# 05_CAMERA_HDMI.net
KiCad netlist of a schematic drawn in Altium Designer
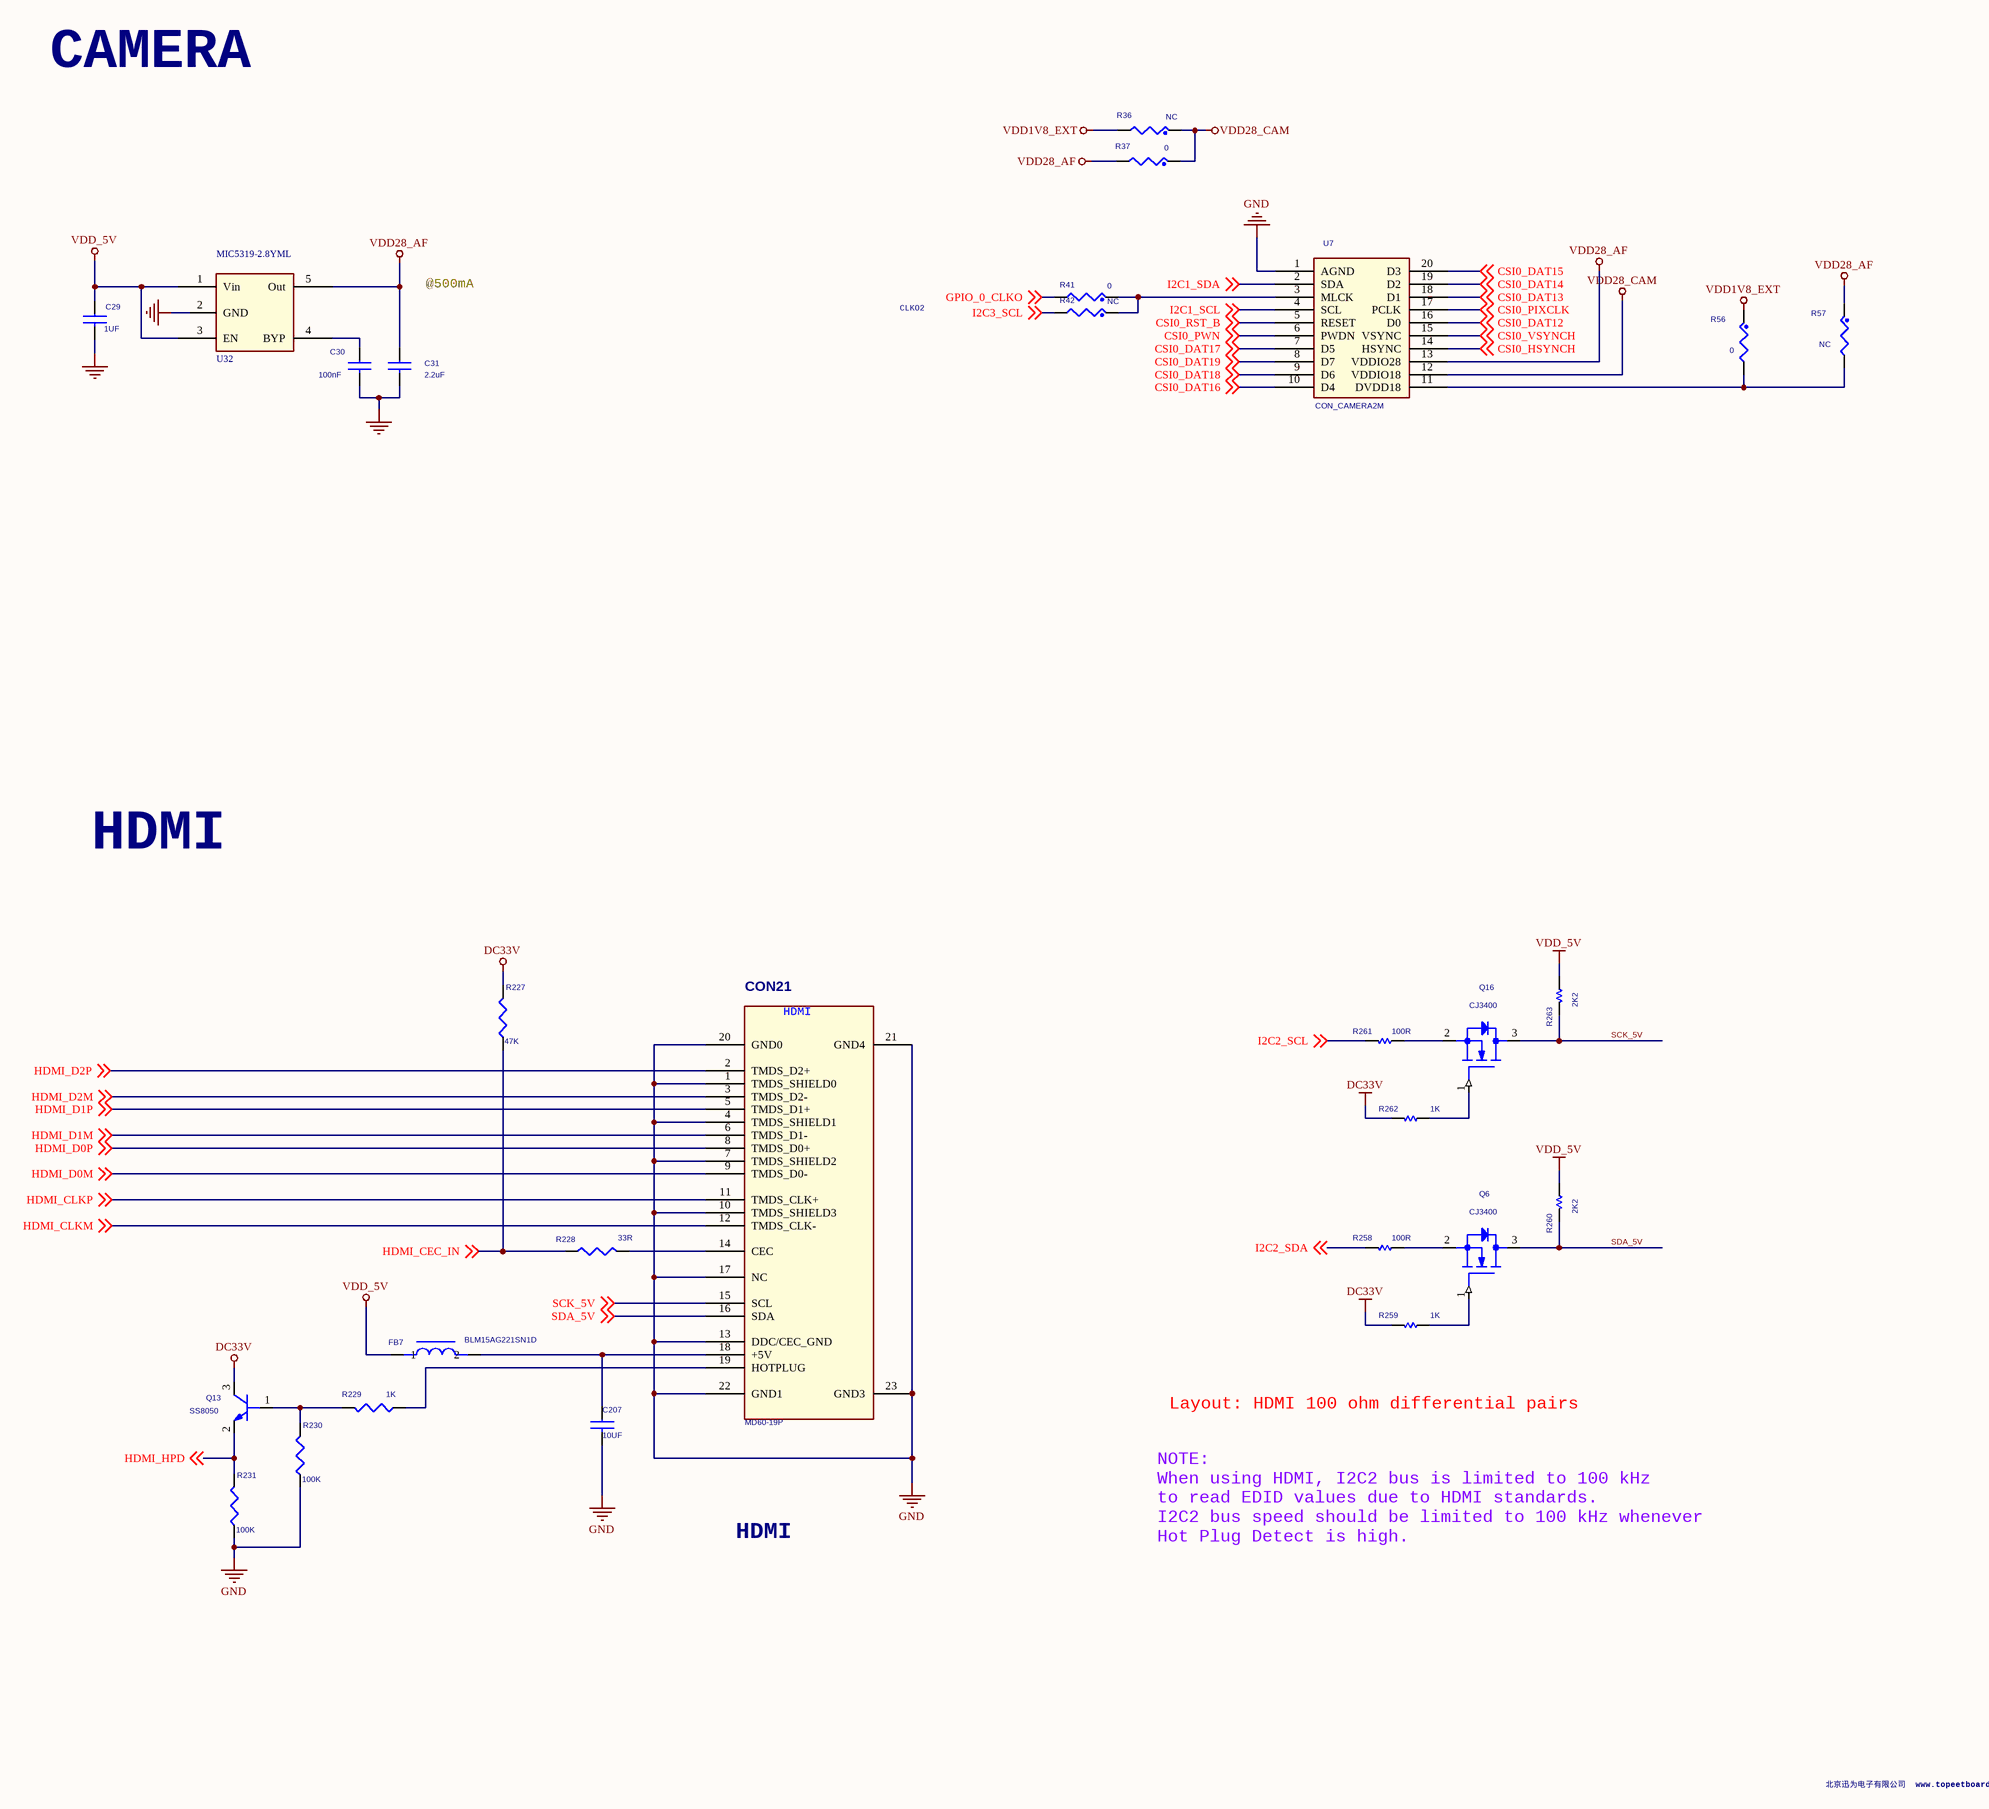
[diagram p0: 05 CAMERA, HDMI.SchDoc]

(export (version "E")
  (design (tool "Eeschema 10.0.6"))
  (components
    (comp (ref "C29") (value "1UF") (footprint "C0603") (libsource (lib "*") (part "C0603_0")))
    (comp (ref "C30") (value "100nF") (footprint "C0603") (libsource (lib "*") (part "C0603_0")))
    (comp (ref "C31") (value "2.2uF") (footprint "C0603") (libsource (lib "*") (part "C0603_0")))
    (comp (ref "C207") (value "10UF") (footprint "C1608") (libsource (lib "*") (part "C1608_Dup1")))
    (comp (ref "CON21") (value "MD60-19P") (footprint "MD60-19P") (libsource (lib "*") (part "MD60-19P_4")))
    (comp (ref "FB7")
      (value "BLM15AG221SN1D")
      (footprint "FB2012")
      (libsource (lib "*") (part "HCB2012KF-300T50_1"))
    )
    (comp (ref "Q6") (value "CJ3400") (libsource (lib "*") (part "NDS351N/SOT_0")))
    (comp (ref "Q13") (value "SS8050") (libsource (lib "*") (part "L14P2/TO_1")))
    (comp (ref "Q16") (value "CJ3400") (libsource (lib "*") (part "NDS351N/SOT_0")))
    (comp (ref "R36")
      (value "NC")
      (description "RES MF 33 OHM 1/16W 5% 0402")
      (fields (field (name "TOLERANCE") "5%"))
      (libsource (lib "*") (part "RES_Dup1"))
    )
    (comp (ref "R37")
      (value "0")
      (description "RES MF 33 OHM 1/16W 5% 0402")
      (fields (field (name "TOLERANCE") "5%"))
      (libsource (lib "*") (part "RES_Dup1"))
    )
    (comp (ref "R41")
      (value "0")
      (description "RES MF 33 OHM 1/16W 5% 0402")
      (fields (field (name "TOLERANCE") "5%"))
      (libsource (lib "*") (part "RES_Dup1"))
    )
    (comp (ref "R42")
      (value "NC")
      (description "RES MF 33 OHM 1/16W 5% 0402")
      (fields (field (name "TOLERANCE") "5%"))
      (libsource (lib "*") (part "RES_Dup1"))
    )
    (comp (ref "R56")
      (value "0")
      (description "RES MF 33 OHM 1/16W 5% 0402")
      (fields (field (name "TOLERANCE") "5%"))
      (libsource (lib "*") (part "RES_Dup1"))
    )
    (comp (ref "R57")
      (value "NC")
      (description "RES MF 33 OHM 1/16W 5% 0402")
      (fields (field (name "TOLERANCE") "5%"))
      (libsource (lib "*") (part "RES_Dup1"))
    )
    (comp (ref "R227") (value "47K") (footprint "R1005") (libsource (lib "*") (part "R1005_0_Dup2")))
    (comp (ref "R228") (value "33R") (footprint "R1005") (libsource (lib "*") (part "R1005_0_Dup2")))
    (comp (ref "R229") (value "1K") (footprint "R1005") (libsource (lib "*") (part "R1005_0_Dup2")))
    (comp (ref "R230") (value "100K") (footprint "R1005") (libsource (lib "*") (part "R1005_0_Dup2")))
    (comp (ref "R231") (value "100K") (footprint "R1005") (libsource (lib "*") (part "R1005_0_Dup2")))
    (comp (ref "R258") (value "100R") (libsource (lib "*") (part "SMALL R1")))
    (comp (ref "R259") (value "1K") (libsource (lib "*") (part "SMALL R1")))
    (comp (ref "R260") (value "2K2") (libsource (lib "*") (part "SMALL R1")))
    (comp (ref "R261") (value "100R") (libsource (lib "*") (part "SMALL R1")))
    (comp (ref "R262") (value "1K") (libsource (lib "*") (part "SMALL R1")))
    (comp (ref "R263") (value "2K2") (libsource (lib "*") (part "SMALL R1")))
    (comp (ref "U7") (value "CON_CAMERA2M") (libsource (lib "*") (part "CON20_0")))
    (comp (ref "U32") (value "MIC5319-2.8YML") (libsource (lib "*") (part "MP1541_0")))
  )
  (nets
    (net (code "1") (name "CSI0_DAT12") (class "Default")
      (node (ref "U7") (pin "16") (pinfunction "D0_16") (pintype "passive"))
    )
    (net (code "2") (name "CSI0_DAT13") (class "Default")
      (node (ref "U7") (pin "18") (pinfunction "D1_18") (pintype "passive"))
    )
    (net (code "3") (name "CSI0_DAT14") (class "Default")
      (node (ref "U7") (pin "19") (pinfunction "D2_19") (pintype "passive"))
    )
    (net (code "4") (name "CSI0_DAT15") (class "Default")
      (node (ref "U7") (pin "20") (pinfunction "D3_20") (pintype "passive"))
    )
    (net (code "5") (name "CSI0_DAT16") (class "Default")
      (node (ref "U7") (pin "10") (pinfunction "D4_10") (pintype "passive"))
    )
    (net (code "6") (name "CSI0_DAT17") (class "Default")
      (node (ref "U7") (pin "7") (pinfunction "D5_7") (pintype "passive"))
    )
    (net (code "7") (name "CSI0_DAT18") (class "Default")
      (node (ref "U7") (pin "9") (pinfunction "D6_9") (pintype "passive"))
    )
    (net (code "8") (name "CSI0_DAT19") (class "Default")
      (node (ref "U7") (pin "8") (pinfunction "D7_8") (pintype "passive"))
    )
    (net (code "9") (name "CSI0_HSYNCH") (class "Default")
      (node (ref "U7") (pin "14") (pinfunction "HSYNC_14") (pintype "passive"))
    )
    (net (code "10") (name "CSI0_PIXCLK") (class "Default")
      (node (ref "U7") (pin "17") (pinfunction "PCLK_17") (pintype "passive"))
    )
    (net (code "11") (name "CSI0_PWN") (class "Default")
      (node (ref "U7") (pin "6") (pinfunction "PWDN_6") (pintype "passive"))
    )
    (net (code "12") (name "CSI0_RST_B") (class "Default")
      (node (ref "U7") (pin "5") (pinfunction "RESET_5") (pintype "passive"))
    )
    (net (code "13") (name "CSI0_VSYNCH") (class "Default")
      (node (ref "U7") (pin "15") (pinfunction "VSYNC_15") (pintype "passive"))
    )
    (net (code "14") (name "DC33V") (class "Default")
      (node (ref "Q13") (pin "3") (pinfunction "COLLECTOR_3") (pintype "passive"))
      (node (ref "R227") (pin "2") (pinfunction "2_2") (pintype "passive"))
      (node (ref "R259") (pin "2") (pinfunction "2_2") (pintype "passive"))
      (node (ref "R262") (pin "2") (pinfunction "2_2") (pintype "passive"))
    )
    (net (code "15") (name "GND") (class "Default")
      (node (ref "C207") (pin "2") (pinfunction "2_2") (pintype "passive"))
      (node (ref "C29") (pin "2") (pinfunction "2_2") (pintype "passive"))
      (node (ref "C30") (pin "2") (pinfunction "2_2") (pintype "passive"))
      (node (ref "C31") (pin "2") (pinfunction "2_2") (pintype "passive"))
      (node (ref "CON21") (pin "1") (pinfunction "TMDS_SHIELD0_1") (pintype "passive"))
      (node (ref "CON21") (pin "10") (pinfunction "TMDS_SHIELD3_10") (pintype "passive"))
      (node (ref "CON21") (pin "13") (pinfunction "DDC/CEC_GND_13") (pintype "passive"))
      (node (ref "CON21") (pin "17") (pinfunction "NC_17") (pintype "passive"))
      (node (ref "CON21") (pin "20") (pinfunction "GND0_20") (pintype "power_in"))
      (node (ref "CON21") (pin "21") (pinfunction "GND4_21") (pintype "power_in"))
      (node (ref "CON21") (pin "22") (pinfunction "GND1_22") (pintype "power_in"))
      (node (ref "CON21") (pin "23") (pinfunction "GND3_23") (pintype "power_in"))
      (node (ref "CON21") (pin "4") (pinfunction "TMDS_SHIELD1_4") (pintype "passive"))
      (node (ref "CON21") (pin "7") (pinfunction "TMDS_SHIELD2_7") (pintype "passive"))
      (node (ref "R230") (pin "1") (pinfunction "1_1") (pintype "passive"))
      (node (ref "R231") (pin "1") (pinfunction "1_1") (pintype "passive"))
      (node (ref "U32") (pin "2") (pinfunction "GND_2") (pintype "passive"))
      (node (ref "U7") (pin "1") (pinfunction "AGND_1") (pintype "power_in"))
    )
    (net (code "16") (name "GPIO_0_CLKO") (class "Default")
      (node (ref "R41") (pin "2") (pinfunction "2_2") (pintype "passive"))
    )
    (net (code "17") (name "HDMI_CEC_IN") (class "Default")
      (node (ref "R227") (pin "1") (pinfunction "1_1") (pintype "passive"))
      (node (ref "R228") (pin "1") (pinfunction "1_1") (pintype "passive"))
    )
    (net (code "18") (name "HDMI_CLKM") (class "Default")
      (node (ref "CON21") (pin "12") (pinfunction "TMDS_CLK-_12") (pintype "passive"))
    )
    (net (code "19") (name "HDMI_CLKP") (class "Default")
      (node (ref "CON21") (pin "11") (pinfunction "TMDS_CLK+_11") (pintype "passive"))
    )
    (net (code "20") (name "HDMI_D0M") (class "Default")
      (node (ref "CON21") (pin "9") (pinfunction "TMDS_D0-_9") (pintype "power_in"))
    )
    (net (code "21") (name "HDMI_D0P") (class "Default")
      (node (ref "CON21") (pin "8") (pinfunction "TMDS_D0+_8") (pintype "passive"))
    )
    (net (code "22") (name "HDMI_D1M") (class "Default")
      (node (ref "CON21") (pin "6") (pinfunction "TMDS_D1-_6") (pintype "passive"))
    )
    (net (code "23") (name "HDMI_D1P") (class "Default")
      (node (ref "CON21") (pin "5") (pinfunction "TMDS_D1+_5") (pintype "passive"))
    )
    (net (code "24") (name "HDMI_D2M") (class "Default")
      (node (ref "CON21") (pin "3") (pinfunction "TMDS_D2-_3") (pintype "passive"))
    )
    (net (code "25") (name "HDMI_D2P") (class "Default")
      (node (ref "CON21") (pin "2") (pinfunction "TMDS_D2+_2") (pintype "passive"))
    )
    (net (code "26") (name "HDMI_HPD") (class "Default")
      (node (ref "Q13") (pin "2") (pinfunction "EMITTER_2") (pintype "passive"))
      (node (ref "R231") (pin "2") (pinfunction "2_2") (pintype "passive"))
    )
    (net (code "27") (name "I2C1_SCL") (class "Default")
      (node (ref "U7") (pin "4") (pinfunction "SCL_4") (pintype "passive"))
    )
    (net (code "28") (name "I2C1_SDA") (class "Default")
      (node (ref "U7") (pin "2") (pinfunction "SDA_2") (pintype "passive"))
    )
    (net (code "29") (name "I2C2_SCL") (class "Default")
      (node (ref "R261") (pin "2") (pinfunction "2_2") (pintype "passive"))
    )
    (net (code "30") (name "I2C2_SDA") (class "Default")
      (node (ref "R258") (pin "2") (pinfunction "2_2") (pintype "passive"))
    )
    (net (code "31") (name "I2C3_SCL") (class "Default")
      (node (ref "R42") (pin "2") (pinfunction "2_2") (pintype "passive"))
    )
    (net (code "32") (name "Net-(CON21-+5V)") (class "Default")
      (node (ref "C207") (pin "1") (pinfunction "1_1") (pintype "passive"))
      (node (ref "CON21") (pin "18") (pinfunction "+5V_18") (pintype "passive"))
      (node (ref "FB7") (pin "2") (pinfunction "2_2") (pintype "passive"))
    )
    (net (code "33") (name "Net-(CON21-CEC)") (class "Default")
      (node (ref "CON21") (pin "14") (pinfunction "CEC_14") (pintype "passive"))
      (node (ref "R228") (pin "2") (pinfunction "2_2") (pintype "passive"))
    )
    (net (code "34") (name "Net-(CON21-HOTPLUG)") (class "Default")
      (node (ref "CON21") (pin "19") (pinfunction "HOTPLUG_19") (pintype "passive"))
      (node (ref "R229") (pin "1") (pinfunction "1_1") (pintype "passive"))
    )
    (net (code "35") (name "Net-(Q6-GATE)") (class "Default")
      (node (ref "Q6") (pin "1") (pinfunction "GATE_1") (pintype "input"))
      (node (ref "R259") (pin "1") (pinfunction "1_1") (pintype "passive"))
    )
    (net (code "36") (name "Net-(Q6-SOURCE)") (class "Default")
      (node (ref "Q6") (pin "2") (pinfunction "SOURCE_2") (pintype "passive"))
      (node (ref "R258") (pin "1") (pinfunction "1_1") (pintype "passive"))
    )
    (net (code "37") (name "Net-(Q13-BASE)") (class "Default")
      (node (ref "Q13") (pin "1") (pinfunction "BASE_1") (pintype "passive"))
      (node (ref "R229") (pin "2") (pinfunction "2_2") (pintype "passive"))
      (node (ref "R230") (pin "2") (pinfunction "2_2") (pintype "passive"))
    )
    (net (code "38") (name "Net-(Q16-GATE)") (class "Default")
      (node (ref "Q16") (pin "1") (pinfunction "GATE_1") (pintype "input"))
      (node (ref "R262") (pin "1") (pinfunction "1_1") (pintype "passive"))
    )
    (net (code "39") (name "Net-(Q16-SOURCE)") (class "Default")
      (node (ref "Q16") (pin "2") (pinfunction "SOURCE_2") (pintype "passive"))
      (node (ref "R261") (pin "1") (pinfunction "1_1") (pintype "passive"))
    )
    (net (code "40") (name "Net-(U7-DVDD18)") (class "Default")
      (node (ref "R56") (pin "2") (pinfunction "2_2") (pintype "passive"))
      (node (ref "R57") (pin "2") (pinfunction "2_2") (pintype "passive"))
      (node (ref "U7") (pin "11") (pinfunction "DVDD18_11") (pintype "power_in"))
    )
    (net (code "41") (name "Net-(U7-MLCK)") (class "Default")
      (node (ref "R41") (pin "1") (pinfunction "1_1") (pintype "passive"))
      (node (ref "R42") (pin "1") (pinfunction "1_1") (pintype "passive"))
      (node (ref "U7") (pin "3") (pinfunction "MLCK_3") (pintype "passive"))
    )
    (net (code "42") (name "Net-(U32-BYP)") (class "Default")
      (node (ref "C30") (pin "1") (pinfunction "1_1") (pintype "passive"))
      (node (ref "U32") (pin "4") (pinfunction "BYP_4") (pintype "passive"))
    )
    (net (code "43") (name "SCK_5V") (class "Default")
      (node (ref "CON21") (pin "15") (pinfunction "SCL_15") (pintype "passive"))
      (node (ref "Q16") (pin "3") (pinfunction "DRAIN_3") (pintype "passive"))
      (node (ref "R263") (pin "2") (pinfunction "2_2") (pintype "passive"))
    )
    (net (code "44") (name "SDA_5V") (class "Default")
      (node (ref "CON21") (pin "16") (pinfunction "SDA_16") (pintype "passive"))
      (node (ref "Q6") (pin "3") (pinfunction "DRAIN_3") (pintype "passive"))
      (node (ref "R260") (pin "2") (pinfunction "2_2") (pintype "passive"))
    )
    (net (code "45") (name "VDD1V8_EXT") (class "Default")
      (node (ref "R36") (pin "2") (pinfunction "2_2") (pintype "passive"))
      (node (ref "R56") (pin "1") (pinfunction "1_1") (pintype "passive"))
    )
    (net (code "46") (name "VDD28_AF") (class "Default")
      (node (ref "C31") (pin "1") (pinfunction "1_1") (pintype "passive"))
      (node (ref "R37") (pin "2") (pinfunction "2_2") (pintype "passive"))
      (node (ref "R57") (pin "1") (pinfunction "1_1") (pintype "passive"))
      (node (ref "U32") (pin "5") (pinfunction "Out_5") (pintype "passive"))
      (node (ref "U7") (pin "13") (pinfunction "VDDIO28_13") (pintype "power_in"))
    )
    (net (code "47") (name "VDD28_CAM") (class "Default")
      (node (ref "R36") (pin "1") (pinfunction "1_1") (pintype "passive"))
      (node (ref "R37") (pin "1") (pinfunction "1_1") (pintype "passive"))
      (node (ref "U7") (pin "12") (pinfunction "VDDIO18_12") (pintype "power_in"))
    )
    (net (code "48") (name "VDD_5V") (class "Default")
      (node (ref "C29") (pin "1") (pinfunction "1_1") (pintype "passive"))
      (node (ref "FB7") (pin "1") (pinfunction "1_1") (pintype "passive"))
      (node (ref "R260") (pin "1") (pinfunction "1_1") (pintype "passive"))
      (node (ref "R263") (pin "1") (pinfunction "1_1") (pintype "passive"))
      (node (ref "U32") (pin "1") (pinfunction "Vin_1") (pintype "passive"))
      (node (ref "U32") (pin "3") (pinfunction "EN_3") (pintype "passive"))
    )
  )
)
